# HyperRAM2.net
KiCad netlist of a schematic drawn in Altium Designer
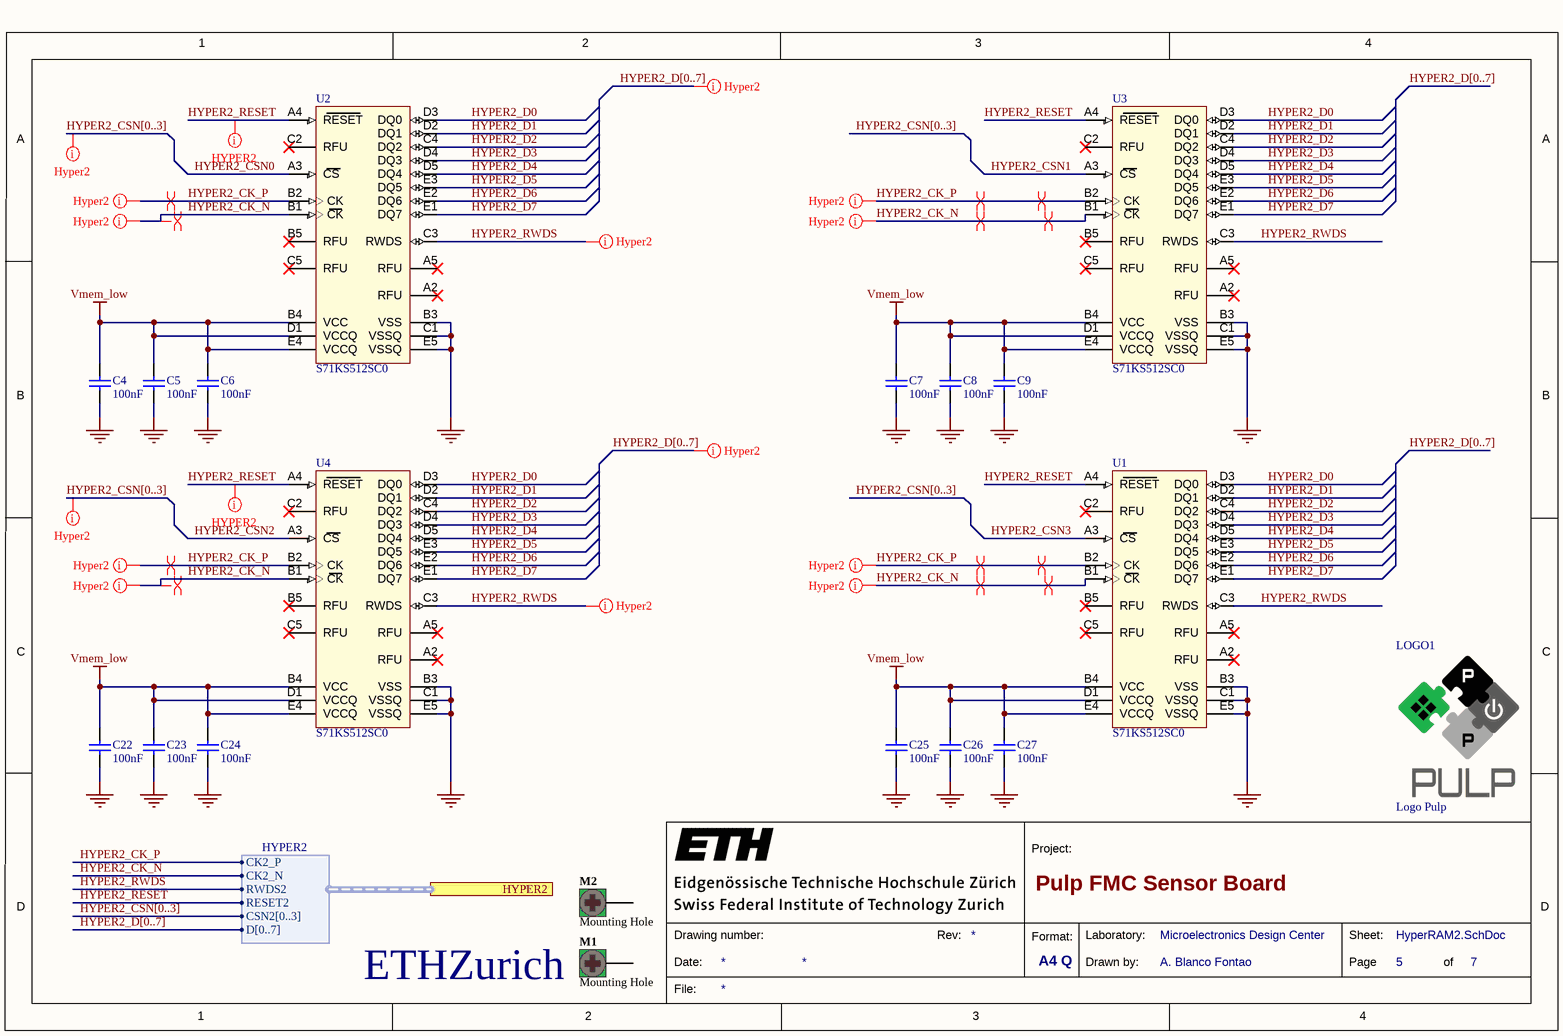
[diagram p0: HyperRAM2.SchDoc]

(export (version "E")
  (design (tool "Eeschema 10.0.6"))
  (components
    (comp (ref "A1")
      (value "Logo ETH Zurich")
      (footprint "eth-zurich_3mm")
      (libsource (lib "ETHZ Vault") (part "CMP-00038-1"))
    )
    (comp (ref "C4")
      (value "100nF")
      (footprint "CAPC0603(1608)100_N")
      (description "CAP 100nF 25V ±10% 0603 (1608 Metric) Thickness 1mm SMD")
      (fields (field (name "TOLERANCE") "Â±10%") (field (name "Comment") "CAP 100nF 25V 0603(1608)"))
      (libsource (lib "Altium Content Vault") (part "CMP-1035-02588-1"))
    )
    (comp (ref "C5")
      (value "100nF")
      (footprint "CAPC0603(1608)100_N")
      (description "CAP 100nF 25V ±10% 0603 (1608 Metric) Thickness 1mm SMD")
      (fields (field (name "TOLERANCE") "Â±10%") (field (name "Comment") "CAP 100nF 25V 0603(1608)"))
      (libsource (lib "Altium Content Vault") (part "CMP-1035-02588-1"))
    )
    (comp (ref "C6")
      (value "100nF")
      (footprint "CAPC0603(1608)100_N")
      (description "CAP 100nF 25V ±10% 0603 (1608 Metric) Thickness 1mm SMD")
      (fields (field (name "TOLERANCE") "Â±10%") (field (name "Comment") "CAP 100nF 25V 0603(1608)"))
      (libsource (lib "Altium Content Vault") (part "CMP-1035-02588-1"))
    )
    (comp (ref "C7")
      (value "100nF")
      (footprint "CAPC0603(1608)100_N")
      (description "CAP 100nF 25V ±10% 0603 (1608 Metric) Thickness 1mm SMD")
      (fields (field (name "TOLERANCE") "Â±10%") (field (name "Comment") "CAP 100nF 25V 0603(1608)"))
      (libsource (lib "Altium Content Vault") (part "CMP-1035-02588-1"))
    )
    (comp (ref "C8")
      (value "100nF")
      (footprint "CAPC0603(1608)100_N")
      (description "CAP 100nF 25V ±10% 0603 (1608 Metric) Thickness 1mm SMD")
      (fields (field (name "TOLERANCE") "Â±10%") (field (name "Comment") "CAP 100nF 25V 0603(1608)"))
      (libsource (lib "Altium Content Vault") (part "CMP-1035-02588-1"))
    )
    (comp (ref "C9")
      (value "100nF")
      (footprint "CAPC0603(1608)100_N")
      (description "CAP 100nF 25V ±10% 0603 (1608 Metric) Thickness 1mm SMD")
      (fields (field (name "TOLERANCE") "Â±10%") (field (name "Comment") "CAP 100nF 25V 0603(1608)"))
      (libsource (lib "Altium Content Vault") (part "CMP-1035-02588-1"))
    )
    (comp (ref "C22")
      (value "100nF")
      (footprint "CAPC0603(1608)100_N")
      (description "CAP 100nF 25V ±10% 0603 (1608 Metric) Thickness 1mm SMD")
      (fields (field (name "TOLERANCE") "Â±10%") (field (name "Comment") "CAP 100nF 25V 0603(1608)"))
      (libsource (lib "Altium Content Vault") (part "CMP-1035-02588-1"))
    )
    (comp (ref "C23")
      (value "100nF")
      (footprint "CAPC0603(1608)100_N")
      (description "CAP 100nF 25V ±10% 0603 (1608 Metric) Thickness 1mm SMD")
      (fields (field (name "TOLERANCE") "Â±10%") (field (name "Comment") "CAP 100nF 25V 0603(1608)"))
      (libsource (lib "Altium Content Vault") (part "CMP-1035-02588-1"))
    )
    (comp (ref "C24")
      (value "100nF")
      (footprint "CAPC0603(1608)100_N")
      (description "CAP 100nF 25V ±10% 0603 (1608 Metric) Thickness 1mm SMD")
      (fields (field (name "TOLERANCE") "Â±10%") (field (name "Comment") "CAP 100nF 25V 0603(1608)"))
      (libsource (lib "Altium Content Vault") (part "CMP-1035-02588-1"))
    )
    (comp (ref "C25")
      (value "100nF")
      (footprint "CAPC0603(1608)100_N")
      (description "CAP 100nF 25V ±10% 0603 (1608 Metric) Thickness 1mm SMD")
      (fields (field (name "TOLERANCE") "Â±10%") (field (name "Comment") "CAP 100nF 25V 0603(1608)"))
      (libsource (lib "Altium Content Vault") (part "CMP-1035-02588-1"))
    )
    (comp (ref "C26")
      (value "100nF")
      (footprint "CAPC0603(1608)100_N")
      (description "CAP 100nF 25V ±10% 0603 (1608 Metric) Thickness 1mm SMD")
      (fields (field (name "TOLERANCE") "Â±10%") (field (name "Comment") "CAP 100nF 25V 0603(1608)"))
      (libsource (lib "Altium Content Vault") (part "CMP-1035-02588-1"))
    )
    (comp (ref "C27")
      (value "100nF")
      (footprint "CAPC0603(1608)100_N")
      (description "CAP 100nF 25V ±10% 0603 (1608 Metric) Thickness 1mm SMD")
      (fields (field (name "TOLERANCE") "Â±10%") (field (name "Comment") "CAP 100nF 25V 0603(1608)"))
      (libsource (lib "Altium Content Vault") (part "CMP-1035-02588-1"))
    )
    (comp (ref "LOGO1")
      (value "Logo Pulp")
      (footprint "Logo Pulp")
      (description "4 Layers: only valid for layer stack as defined for the TestBoards")
      (libsource (lib "ETHZ Vault") (part "CMP-00145-1"))
    )
    (comp (ref "M1")
      (value "Mounting Hole")
      (footprint "Hole M3")
      (description "Mounting Hole, 7.2mm pad, 3.2mm plated hole")
      (libsource (lib "ETHZ Vault") (part "Hole"))
    )
    (comp (ref "M2")
      (value "Mounting Hole")
      (footprint "Hole M3")
      (description "Mounting Hole, 7.2mm pad, 3.2mm plated hole")
      (libsource (lib "ETHZ Vault") (part "Hole"))
    )
    (comp (ref "U1")
      (value "S71KS512SC0")
      (footprint "FBGA24_A-130")
      (description "Cypress 64Mbit DRAM 24FBGA HyperRam")
      (libsource (lib "hyperRAM") (part "S80KS5122"))
    )
    (comp (ref "U2")
      (value "S71KS512SC0")
      (footprint "FBGA24_A-130")
      (description "Cypress 64Mbit DRAM 24FBGA HyperRam")
      (libsource (lib "hyperRAM") (part "S80KS5122"))
    )
    (comp (ref "U3")
      (value "S71KS512SC0")
      (footprint "FBGA24_A-130")
      (description "Cypress 64Mbit DRAM 24FBGA HyperRam")
      (libsource (lib "hyperRAM") (part "S80KS5122"))
    )
    (comp (ref "U4")
      (value "S71KS512SC0")
      (footprint "FBGA24_A-130")
      (description "Cypress 64Mbit DRAM 24FBGA HyperRam")
      (libsource (lib "hyperRAM") (part "S80KS5122"))
    )
  )
  (nets
    (net (code "2") (name "/HYPER2_CK_N") (class "Default")
      (node (ref "U1") (pin "B1") (pinfunction "CK_B1") (pintype "input"))
      (node (ref "U2") (pin "B1") (pinfunction "CK_B1") (pintype "input"))
      (node (ref "U3") (pin "B1") (pinfunction "CK_B1") (pintype "input"))
      (node (ref "U4") (pin "B1") (pinfunction "CK_B1") (pintype "input"))
    )
    (net (code "3") (name "/HYPER2_CK_P") (class "Default")
      (node (ref "U1") (pin "B2") (pinfunction "CK_B2") (pintype "input"))
      (node (ref "U2") (pin "B2") (pinfunction "CK_B2") (pintype "input"))
      (node (ref "U3") (pin "B2") (pinfunction "CK_B2") (pintype "input"))
      (node (ref "U4") (pin "B2") (pinfunction "CK_B2") (pintype "input"))
    )
    (net (code "4") (name "/HYPER2_CSN0") (class "Default")
      (node (ref "U2") (pin "A3") (pinfunction "CS_A3") (pintype "input"))
    )
    (net (code "5") (name "/HYPER2_CSN1") (class "Default")
      (node (ref "U3") (pin "A3") (pinfunction "CS_A3") (pintype "input"))
    )
    (net (code "6") (name "/HYPER2_CSN2") (class "Default")
      (node (ref "U4") (pin "A3") (pinfunction "CS_A3") (pintype "input"))
    )
    (net (code "7") (name "/HYPER2_CSN3") (class "Default")
      (node (ref "U1") (pin "A3") (pinfunction "CS_A3") (pintype "input"))
    )
    (net (code "9") (name "/HYPER2_D0") (class "Default")
      (node (ref "U1") (pin "D3") (pinfunction "DQ0_D3") (pintype "bidirectional"))
      (node (ref "U2") (pin "D3") (pinfunction "DQ0_D3") (pintype "bidirectional"))
      (node (ref "U3") (pin "D3") (pinfunction "DQ0_D3") (pintype "bidirectional"))
      (node (ref "U4") (pin "D3") (pinfunction "DQ0_D3") (pintype "bidirectional"))
    )
    (net (code "10") (name "/HYPER2_D1") (class "Default")
      (node (ref "U1") (pin "D2") (pinfunction "DQ1_D2") (pintype "bidirectional"))
      (node (ref "U2") (pin "D2") (pinfunction "DQ1_D2") (pintype "bidirectional"))
      (node (ref "U3") (pin "D2") (pinfunction "DQ1_D2") (pintype "bidirectional"))
      (node (ref "U4") (pin "D2") (pinfunction "DQ1_D2") (pintype "bidirectional"))
    )
    (net (code "11") (name "/HYPER2_D2") (class "Default")
      (node (ref "U1") (pin "C4") (pinfunction "DQ2_C4") (pintype "bidirectional"))
      (node (ref "U2") (pin "C4") (pinfunction "DQ2_C4") (pintype "bidirectional"))
      (node (ref "U3") (pin "C4") (pinfunction "DQ2_C4") (pintype "bidirectional"))
      (node (ref "U4") (pin "C4") (pinfunction "DQ2_C4") (pintype "bidirectional"))
    )
    (net (code "12") (name "/HYPER2_D3") (class "Default")
      (node (ref "U1") (pin "D4") (pinfunction "DQ3_D4") (pintype "bidirectional"))
      (node (ref "U2") (pin "D4") (pinfunction "DQ3_D4") (pintype "bidirectional"))
      (node (ref "U3") (pin "D4") (pinfunction "DQ3_D4") (pintype "bidirectional"))
      (node (ref "U4") (pin "D4") (pinfunction "DQ3_D4") (pintype "bidirectional"))
    )
    (net (code "13") (name "/HYPER2_D4") (class "Default")
      (node (ref "U1") (pin "D5") (pinfunction "DQ4_D5") (pintype "bidirectional"))
      (node (ref "U2") (pin "D5") (pinfunction "DQ4_D5") (pintype "bidirectional"))
      (node (ref "U3") (pin "D5") (pinfunction "DQ4_D5") (pintype "bidirectional"))
      (node (ref "U4") (pin "D5") (pinfunction "DQ4_D5") (pintype "bidirectional"))
    )
    (net (code "14") (name "/HYPER2_D5") (class "Default")
      (node (ref "U1") (pin "E3") (pinfunction "DQ5_E3") (pintype "bidirectional"))
      (node (ref "U2") (pin "E3") (pinfunction "DQ5_E3") (pintype "bidirectional"))
      (node (ref "U3") (pin "E3") (pinfunction "DQ5_E3") (pintype "bidirectional"))
      (node (ref "U4") (pin "E3") (pinfunction "DQ5_E3") (pintype "bidirectional"))
    )
    (net (code "15") (name "/HYPER2_D6") (class "Default")
      (node (ref "U1") (pin "E2") (pinfunction "DQ6_E2") (pintype "bidirectional"))
      (node (ref "U2") (pin "E2") (pinfunction "DQ6_E2") (pintype "bidirectional"))
      (node (ref "U3") (pin "E2") (pinfunction "DQ6_E2") (pintype "bidirectional"))
      (node (ref "U4") (pin "E2") (pinfunction "DQ6_E2") (pintype "bidirectional"))
    )
    (net (code "16") (name "/HYPER2_D7") (class "Default")
      (node (ref "U1") (pin "E1") (pinfunction "DQ7_E1") (pintype "bidirectional"))
      (node (ref "U2") (pin "E1") (pinfunction "DQ7_E1") (pintype "bidirectional"))
      (node (ref "U3") (pin "E1") (pinfunction "DQ7_E1") (pintype "bidirectional"))
      (node (ref "U4") (pin "E1") (pinfunction "DQ7_E1") (pintype "bidirectional"))
    )
    (net (code "18") (name "/HYPER2_RESET") (class "Default")
      (node (ref "U1") (pin "A4") (pinfunction "RESET_A4") (pintype "input"))
      (node (ref "U2") (pin "A4") (pinfunction "RESET_A4") (pintype "input"))
      (node (ref "U3") (pin "A4") (pinfunction "RESET_A4") (pintype "input"))
      (node (ref "U4") (pin "A4") (pinfunction "RESET_A4") (pintype "input"))
    )
    (net (code "19") (name "/HYPER2_RWDS") (class "Default")
      (node (ref "U1") (pin "C3") (pinfunction "RWDS_C3") (pintype "bidirectional"))
      (node (ref "U2") (pin "C3") (pinfunction "RWDS_C3") (pintype "bidirectional"))
      (node (ref "U3") (pin "C3") (pinfunction "RWDS_C3") (pintype "bidirectional"))
      (node (ref "U4") (pin "C3") (pinfunction "RWDS_C3") (pintype "bidirectional"))
    )
    (net (code "21") (name "GND") (class "Default")
      (node (ref "C22") (pin "1") (pinfunction "1_1") (pintype "passive"))
      (node (ref "C23") (pin "1") (pinfunction "1_1") (pintype "passive"))
      (node (ref "C24") (pin "1") (pinfunction "1_1") (pintype "passive"))
      (node (ref "C25") (pin "1") (pinfunction "1_1") (pintype "passive"))
      (node (ref "C26") (pin "1") (pinfunction "1_1") (pintype "passive"))
      (node (ref "C27") (pin "1") (pinfunction "1_1") (pintype "passive"))
      (node (ref "C4") (pin "1") (pinfunction "1_1") (pintype "passive"))
      (node (ref "C5") (pin "1") (pinfunction "1_1") (pintype "passive"))
      (node (ref "C6") (pin "1") (pinfunction "1_1") (pintype "passive"))
      (node (ref "C7") (pin "1") (pinfunction "1_1") (pintype "passive"))
      (node (ref "C8") (pin "1") (pinfunction "1_1") (pintype "passive"))
      (node (ref "C9") (pin "1") (pinfunction "1_1") (pintype "passive"))
      (node (ref "U1") (pin "B3") (pinfunction "VSS_B3") (pintype "passive"))
      (node (ref "U1") (pin "C1") (pinfunction "VSSQ_C1") (pintype "passive"))
      (node (ref "U1") (pin "E5") (pinfunction "VSSQ_E5") (pintype "passive"))
      (node (ref "U2") (pin "B3") (pinfunction "VSS_B3") (pintype "passive"))
      (node (ref "U2") (pin "C1") (pinfunction "VSSQ_C1") (pintype "passive"))
      (node (ref "U2") (pin "E5") (pinfunction "VSSQ_E5") (pintype "passive"))
      (node (ref "U3") (pin "B3") (pinfunction "VSS_B3") (pintype "passive"))
      (node (ref "U3") (pin "C1") (pinfunction "VSSQ_C1") (pintype "passive"))
      (node (ref "U3") (pin "E5") (pinfunction "VSSQ_E5") (pintype "passive"))
      (node (ref "U4") (pin "B3") (pinfunction "VSS_B3") (pintype "passive"))
      (node (ref "U4") (pin "C1") (pinfunction "VSSQ_C1") (pintype "passive"))
      (node (ref "U4") (pin "E5") (pinfunction "VSSQ_E5") (pintype "passive"))
    )
    (net (code "22") (name "Vmem_low") (class "Default")
      (node (ref "C22") (pin "2") (pinfunction "2_2") (pintype "passive"))
      (node (ref "C23") (pin "2") (pinfunction "2_2") (pintype "passive"))
      (node (ref "C24") (pin "2") (pinfunction "2_2") (pintype "passive"))
      (node (ref "C25") (pin "2") (pinfunction "2_2") (pintype "passive"))
      (node (ref "C26") (pin "2") (pinfunction "2_2") (pintype "passive"))
      (node (ref "C27") (pin "2") (pinfunction "2_2") (pintype "passive"))
      (node (ref "C4") (pin "2") (pinfunction "2_2") (pintype "passive"))
      (node (ref "C5") (pin "2") (pinfunction "2_2") (pintype "passive"))
      (node (ref "C6") (pin "2") (pinfunction "2_2") (pintype "passive"))
      (node (ref "C7") (pin "2") (pinfunction "2_2") (pintype "passive"))
      (node (ref "C8") (pin "2") (pinfunction "2_2") (pintype "passive"))
      (node (ref "C9") (pin "2") (pinfunction "2_2") (pintype "passive"))
      (node (ref "U1") (pin "B4") (pinfunction "VCC_B4") (pintype "passive"))
      (node (ref "U1") (pin "D1") (pinfunction "VCCQ_D1") (pintype "passive"))
      (node (ref "U1") (pin "E4") (pinfunction "VCCQ_E4") (pintype "passive"))
      (node (ref "U2") (pin "B4") (pinfunction "VCC_B4") (pintype "passive"))
      (node (ref "U2") (pin "D1") (pinfunction "VCCQ_D1") (pintype "passive"))
      (node (ref "U2") (pin "E4") (pinfunction "VCCQ_E4") (pintype "passive"))
      (node (ref "U3") (pin "B4") (pinfunction "VCC_B4") (pintype "passive"))
      (node (ref "U3") (pin "D1") (pinfunction "VCCQ_D1") (pintype "passive"))
      (node (ref "U3") (pin "E4") (pinfunction "VCCQ_E4") (pintype "passive"))
      (node (ref "U4") (pin "B4") (pinfunction "VCC_B4") (pintype "passive"))
      (node (ref "U4") (pin "D1") (pinfunction "VCCQ_D1") (pintype "passive"))
      (node (ref "U4") (pin "E4") (pinfunction "VCCQ_E4") (pintype "passive"))
    )
    (net (code "23") (name "unconnected-(M1-Pad1)") (class "Default")
      (node (ref "M1") (pin "1") (pinfunction "1_1") (pintype "passive"))
    )
    (net (code "24") (name "unconnected-(M2-Pad1)") (class "Default")
      (node (ref "M2") (pin "1") (pinfunction "1_1") (pintype "passive"))
    )
    (net (code "25") (name "unconnected-(U1-RFU-PadA2)") (class "Default")
      (node (ref "U1") (pin "A2") (pinfunction "RFU_A2") (pintype "passive+no_connect"))
    )
    (net (code "26") (name "unconnected-(U1-RFU-PadA5)") (class "Default")
      (node (ref "U1") (pin "A5") (pinfunction "RFU_A5") (pintype "passive+no_connect"))
    )
    (net (code "27") (name "unconnected-(U1-RFU-PadB5)") (class "Default")
      (node (ref "U1") (pin "B5") (pinfunction "RFU_B5") (pintype "passive+no_connect"))
    )
    (net (code "28") (name "unconnected-(U1-RFU-PadC2)") (class "Default")
      (node (ref "U1") (pin "C2") (pinfunction "RFU_C2") (pintype "passive+no_connect"))
    )
    (net (code "29") (name "unconnected-(U1-RFU-PadC5)") (class "Default")
      (node (ref "U1") (pin "C5") (pinfunction "RFU_C5") (pintype "passive+no_connect"))
    )
    (net (code "30") (name "unconnected-(U2-RFU-PadA2)") (class "Default")
      (node (ref "U2") (pin "A2") (pinfunction "RFU_A2") (pintype "passive+no_connect"))
    )
    (net (code "31") (name "unconnected-(U2-RFU-PadA5)") (class "Default")
      (node (ref "U2") (pin "A5") (pinfunction "RFU_A5") (pintype "passive+no_connect"))
    )
    (net (code "32") (name "unconnected-(U2-RFU-PadB5)") (class "Default")
      (node (ref "U2") (pin "B5") (pinfunction "RFU_B5") (pintype "passive+no_connect"))
    )
    (net (code "33") (name "unconnected-(U2-RFU-PadC2)") (class "Default")
      (node (ref "U2") (pin "C2") (pinfunction "RFU_C2") (pintype "passive+no_connect"))
    )
    (net (code "34") (name "unconnected-(U2-RFU-PadC5)") (class "Default")
      (node (ref "U2") (pin "C5") (pinfunction "RFU_C5") (pintype "passive+no_connect"))
    )
    (net (code "35") (name "unconnected-(U3-RFU-PadA2)") (class "Default")
      (node (ref "U3") (pin "A2") (pinfunction "RFU_A2") (pintype "passive+no_connect"))
    )
    (net (code "36") (name "unconnected-(U3-RFU-PadA5)") (class "Default")
      (node (ref "U3") (pin "A5") (pinfunction "RFU_A5") (pintype "passive+no_connect"))
    )
    (net (code "37") (name "unconnected-(U3-RFU-PadB5)") (class "Default")
      (node (ref "U3") (pin "B5") (pinfunction "RFU_B5") (pintype "passive+no_connect"))
    )
    (net (code "38") (name "unconnected-(U3-RFU-PadC2)") (class "Default")
      (node (ref "U3") (pin "C2") (pinfunction "RFU_C2") (pintype "passive+no_connect"))
    )
    (net (code "39") (name "unconnected-(U3-RFU-PadC5)") (class "Default")
      (node (ref "U3") (pin "C5") (pinfunction "RFU_C5") (pintype "passive+no_connect"))
    )
    (net (code "40") (name "unconnected-(U4-RFU-PadA2)") (class "Default")
      (node (ref "U4") (pin "A2") (pinfunction "RFU_A2") (pintype "passive+no_connect"))
    )
    (net (code "41") (name "unconnected-(U4-RFU-PadA5)") (class "Default")
      (node (ref "U4") (pin "A5") (pinfunction "RFU_A5") (pintype "passive+no_connect"))
    )
    (net (code "42") (name "unconnected-(U4-RFU-PadB5)") (class "Default")
      (node (ref "U4") (pin "B5") (pinfunction "RFU_B5") (pintype "passive+no_connect"))
    )
    (net (code "43") (name "unconnected-(U4-RFU-PadC2)") (class "Default")
      (node (ref "U4") (pin "C2") (pinfunction "RFU_C2") (pintype "passive+no_connect"))
    )
    (net (code "44") (name "unconnected-(U4-RFU-PadC5)") (class "Default")
      (node (ref "U4") (pin "C5") (pinfunction "RFU_C5") (pintype "passive+no_connect"))
    )
  )
)
